# P_10_WIFI_Bluetooth.net
KiCad netlist of a schematic drawn in Altium Designer
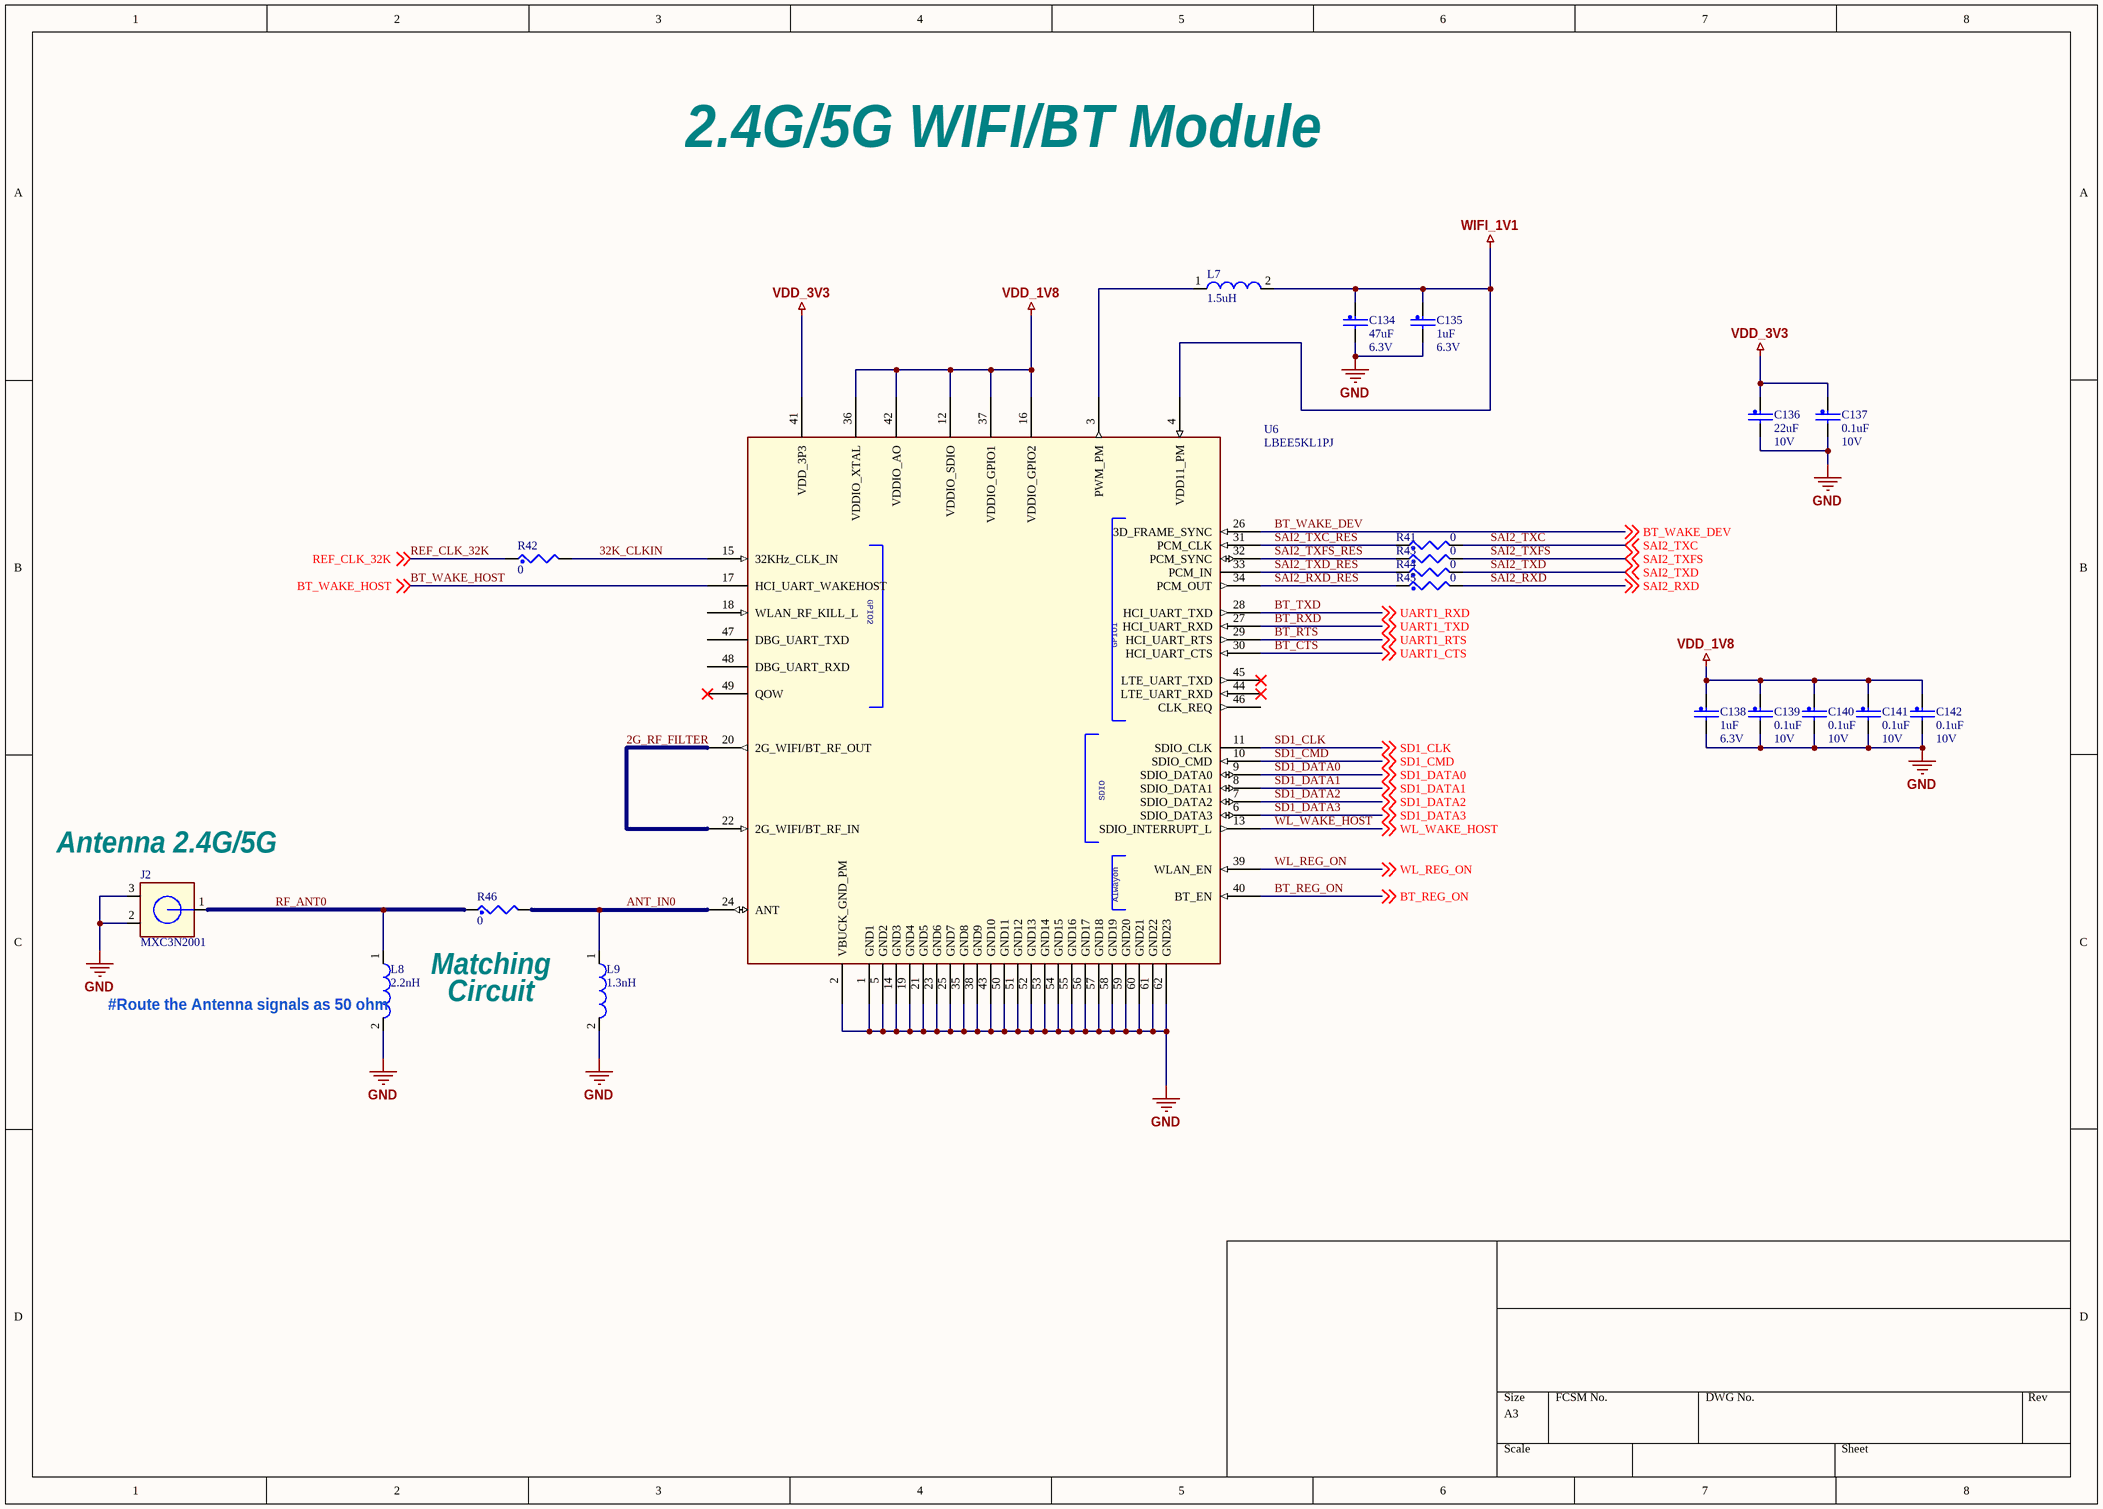
[diagram p0: P[10]WIFI_Bluetooth.SchDoc]

(export (version "E")
  (design (tool "Eeschema 10.0.6"))
  (components
    (comp (ref "C134")
      (value "47uF")
      (footprint "0805_CC")
      (fields (field (name "VOLTAGE") "6.3V"))
      (libsource (lib "AA_iMX8_M_") (part "CAP_NP"))
    )
    (comp (ref "C135")
      (value "1uF")
      (footprint "0201_CC - C")
      (fields (field (name "VOLTAGE") "6.3V"))
      (libsource (lib "AA_iMX8_M_") (part "CAP_NP"))
    )
    (comp (ref "C136")
      (value "22uF")
      (footprint "0603_CC")
      (fields (field (name "VOLTAGE") "10V"))
      (libsource (lib "AA_iMX8_M_") (part "CAP_NP"))
    )
    (comp (ref "C137")
      (value "0.1uF")
      (footprint "0201_CC - C")
      (fields (field (name "VOLTAGE") "10V"))
      (libsource (lib "AA_iMX8_M_") (part "CAP_NP"))
    )
    (comp (ref "C138")
      (value "1uF")
      (footprint "0201_CC - C")
      (fields (field (name "VOLTAGE") "6.3V"))
      (libsource (lib "AA_iMX8_M_") (part "CAP_NP"))
    )
    (comp (ref "C139")
      (value "0.1uF")
      (footprint "0201_CC - C")
      (fields (field (name "VOLTAGE") "10V"))
      (libsource (lib "AA_iMX8_M_") (part "CAP_NP"))
    )
    (comp (ref "C140")
      (value "0.1uF")
      (footprint "0201_CC - C")
      (fields (field (name "VOLTAGE") "10V"))
      (libsource (lib "AA_iMX8_M_") (part "CAP_NP"))
    )
    (comp (ref "C141")
      (value "0.1uF")
      (footprint "0201_CC - C")
      (fields (field (name "VOLTAGE") "10V"))
      (libsource (lib "AA_iMX8_M_") (part "CAP_NP"))
    )
    (comp (ref "C142")
      (value "0.1uF")
      (footprint "0201_CC - C")
      (fields (field (name "VOLTAGE") "10V"))
      (libsource (lib "AA_iMX8_M_") (part "CAP_NP"))
    )
    (comp (ref "J2")
      (value "MXC3N2001")
      (footprint "CON_3_UFL_R_SMT")
      (description "CON 1 COAX SKT SMT 55H AU\\By Arman Arvand")
      (libsource (lib "AA_iMX8_M_") (part "UFL"))
    )
    (comp (ref "L7")
      (value "1.5uH")
      (footprint "INDC2016X100N")
      (libsource (lib "AA_iMX8_M_") (part "INDUCTOR"))
    )
    (comp (ref "L8")
      (value "2.2nH")
      (footprint "0402_CC_IND")
      (libsource (lib "AA_iMX8_M_") (part "INDUCTOR"))
    )
    (comp (ref "L9")
      (value "1.3nH")
      (footprint "0402_CC_IND")
      (libsource (lib "AA_iMX8_M_") (part "INDUCTOR"))
    )
    (comp (ref "R41") (value "0") (footprint "0402_CC") (libsource (lib "AA_iMX8_M_") (part "RES")))
    (comp (ref "R42") (value "0") (footprint "0402_CC") (libsource (lib "AA_iMX8_M_") (part "RES")))
    (comp (ref "R43") (value "0") (footprint "0402_CC") (libsource (lib "AA_iMX8_M_") (part "RES")))
    (comp (ref "R44") (value "0") (footprint "0402_CC") (libsource (lib "AA_iMX8_M_") (part "RES")))
    (comp (ref "R45") (value "0") (footprint "0402_CC") (libsource (lib "AA_iMX8_M_") (part "RES")))
    (comp (ref "R46") (value "0") (footprint "0402_CC") (libsource (lib "AA_iMX8_M_") (part "RES")))
    (comp (ref "U6")
      (value "LBEE5KL1PJ")
      (footprint "LQFN62_0P6_7P6X7P4")
      (description "LBEE5KL1PJ_QFN62\\By Arman Arvand")
      (libsource (lib "AA_iMX8_M_") (part "LBEE5KL1PJ_QFN62"))
    )
  )
  (nets
    (net (code "1") (name "/2G_RF_FILTER") (class "Default")
      (node (ref "U6") (pin "20") (pinfunction "2G_WIFI/BT_RF_OUT_20") (pintype "output"))
      (node (ref "U6") (pin "22") (pinfunction "2G_WIFI/BT_RF_IN_22") (pintype "input"))
    )
    (net (code "2") (name "/32K_CLKIN") (class "Default")
      (node (ref "R42") (pin "2") (pinfunction "2_2") (pintype "passive"))
      (node (ref "U6") (pin "15") (pinfunction "32KHz_CLK_IN_15") (pintype "input"))
    )
    (net (code "3") (name "/ANT_IN0") (class "Default")
      (node (ref "L9") (pin "1") (pinfunction "1_1") (pintype "passive"))
      (node (ref "R46") (pin "2") (pinfunction "2_2") (pintype "passive"))
      (node (ref "U6") (pin "24") (pinfunction "ANT_24") (pintype "bidirectional"))
    )
    (net (code "4") (name "/RF_ANT0") (class "Default")
      (node (ref "J2") (pin "1") (pinfunction "CTR_1") (pintype "passive"))
      (node (ref "L8") (pin "1") (pinfunction "1_1") (pintype "passive"))
      (node (ref "R46") (pin "1") (pinfunction "1_1") (pintype "passive"))
    )
    (net (code "5") (name "/SAI2_RXD_RES") (class "Default")
      (node (ref "R45") (pin "1") (pinfunction "1_1") (pintype "passive"))
      (node (ref "U6") (pin "34") (pinfunction "PCM_OUT_34") (pintype "output"))
    )
    (net (code "6") (name "/SAI2_TXC_RES") (class "Default")
      (node (ref "R41") (pin "1") (pinfunction "1_1") (pintype "passive"))
      (node (ref "U6") (pin "31") (pinfunction "PCM_CLK_31") (pintype "input"))
    )
    (net (code "7") (name "/SAI2_TXD_RES") (class "Default")
      (node (ref "R44") (pin "1") (pinfunction "1_1") (pintype "passive"))
      (node (ref "U6") (pin "33") (pinfunction "PCM_IN_33") (pintype "open_collector"))
    )
    (net (code "8") (name "/SAI2_TXFS_RES") (class "Default")
      (node (ref "R43") (pin "1") (pinfunction "1_1") (pintype "passive"))
      (node (ref "U6") (pin "32") (pinfunction "PCM_SYNC_32") (pintype "bidirectional"))
    )
    (net (code "9") (name "BT_REG_ON") (class "Default")
      (node (ref "U6") (pin "40") (pinfunction "BT_EN_40") (pintype "input"))
    )
    (net (code "10") (name "BT_WAKE_DEV") (class "Default")
      (node (ref "U6") (pin "26") (pinfunction "3D_FRAME_SYNC_26") (pintype "input"))
    )
    (net (code "11") (name "BT_WAKE_HOST") (class "Default")
      (node (ref "U6") (pin "17") (pinfunction "HCI_UART_WAKEHOST_17") (pintype "open_collector"))
    )
    (net (code "12") (name "GND") (class "Default")
      (node (ref "C134") (pin "2") (pinfunction "2_2") (pintype "passive"))
      (node (ref "C135") (pin "2") (pinfunction "2_2") (pintype "passive"))
      (node (ref "C136") (pin "2") (pinfunction "2_2") (pintype "passive"))
      (node (ref "C137") (pin "2") (pinfunction "2_2") (pintype "passive"))
      (node (ref "C138") (pin "2") (pinfunction "2_2") (pintype "passive"))
      (node (ref "C139") (pin "2") (pinfunction "2_2") (pintype "passive"))
      (node (ref "C140") (pin "2") (pinfunction "2_2") (pintype "passive"))
      (node (ref "C141") (pin "2") (pinfunction "2_2") (pintype "passive"))
      (node (ref "C142") (pin "2") (pinfunction "2_2") (pintype "passive"))
      (node (ref "J2") (pin "2") (pinfunction "GND1_2") (pintype "passive"))
      (node (ref "J2") (pin "3") (pinfunction "GND2_3") (pintype "passive"))
      (node (ref "L8") (pin "2") (pinfunction "2_2") (pintype "passive"))
      (node (ref "L9") (pin "2") (pinfunction "2_2") (pintype "passive"))
      (node (ref "U6") (pin "1") (pinfunction "GND1_1") (pintype "power_in"))
      (node (ref "U6") (pin "14") (pinfunction "GND3_14") (pintype "power_in"))
      (node (ref "U6") (pin "19") (pinfunction "GND4_19") (pintype "power_in"))
      (node (ref "U6") (pin "2") (pinfunction "VBUCK_GND_PM_2") (pintype "power_in"))
      (node (ref "U6") (pin "21") (pinfunction "GND5_21") (pintype "power_in"))
      (node (ref "U6") (pin "23") (pinfunction "GND6_23") (pintype "power_in"))
      (node (ref "U6") (pin "25") (pinfunction "GND7_25") (pintype "power_in"))
      (node (ref "U6") (pin "35") (pinfunction "GND8_35") (pintype "power_in"))
      (node (ref "U6") (pin "38") (pinfunction "GND9_38") (pintype "power_in"))
      (node (ref "U6") (pin "43") (pinfunction "GND10_43") (pintype "power_in"))
      (node (ref "U6") (pin "5") (pinfunction "GND2_5") (pintype "power_in"))
      (node (ref "U6") (pin "50") (pinfunction "GND11_50") (pintype "power_in"))
      (node (ref "U6") (pin "51") (pinfunction "GND12_51") (pintype "power_in"))
      (node (ref "U6") (pin "52") (pinfunction "GND13_52") (pintype "power_in"))
      (node (ref "U6") (pin "53") (pinfunction "GND14_53") (pintype "power_in"))
      (node (ref "U6") (pin "54") (pinfunction "GND15_54") (pintype "power_in"))
      (node (ref "U6") (pin "55") (pinfunction "GND16_55") (pintype "power_in"))
      (node (ref "U6") (pin "56") (pinfunction "GND17_56") (pintype "power_in"))
      (node (ref "U6") (pin "57") (pinfunction "GND18_57") (pintype "power_in"))
      (node (ref "U6") (pin "58") (pinfunction "GND19_58") (pintype "power_in"))
      (node (ref "U6") (pin "59") (pinfunction "GND20_59") (pintype "power_in"))
      (node (ref "U6") (pin "60") (pinfunction "GND21_60") (pintype "power_in"))
      (node (ref "U6") (pin "61") (pinfunction "GND22_61") (pintype "power_in"))
      (node (ref "U6") (pin "62") (pinfunction "GND23_62") (pintype "power_in"))
    )
    (net (code "13") (name "Net-(U6-PWM_PM)") (class "Default")
      (node (ref "L7") (pin "1") (pinfunction "1_1") (pintype "passive"))
      (node (ref "U6") (pin "3") (pinfunction "PWM_PM_3") (pintype "output"))
    )
    (net (code "14") (name "REF_CLK_32K") (class "Default")
      (node (ref "R42") (pin "1") (pinfunction "1_1") (pintype "passive"))
    )
    (net (code "15") (name "SAI2_RXD") (class "Default")
      (node (ref "R45") (pin "2") (pinfunction "2_2") (pintype "passive"))
    )
    (net (code "16") (name "SAI2_TXC") (class "Default")
      (node (ref "R41") (pin "2") (pinfunction "2_2") (pintype "passive"))
    )
    (net (code "17") (name "SAI2_TXD") (class "Default")
      (node (ref "R44") (pin "2") (pinfunction "2_2") (pintype "passive"))
    )
    (net (code "18") (name "SAI2_TXFS") (class "Default")
      (node (ref "R43") (pin "2") (pinfunction "2_2") (pintype "passive"))
    )
    (net (code "19") (name "SD1_CLK") (class "Default")
      (node (ref "U6") (pin "11") (pinfunction "SDIO_CLK_11") (pintype "open_collector"))
    )
    (net (code "20") (name "SD1_CMD") (class "Default")
      (node (ref "U6") (pin "10") (pinfunction "SDIO_CMD_10") (pintype "input"))
    )
    (net (code "21") (name "SD1_DATA0") (class "Default")
      (node (ref "U6") (pin "9") (pinfunction "SDIO_DATA0_9") (pintype "bidirectional"))
    )
    (net (code "22") (name "SD1_DATA1") (class "Default")
      (node (ref "U6") (pin "8") (pinfunction "SDIO_DATA1_8") (pintype "bidirectional"))
    )
    (net (code "23") (name "SD1_DATA2") (class "Default")
      (node (ref "U6") (pin "7") (pinfunction "SDIO_DATA2_7") (pintype "bidirectional"))
    )
    (net (code "24") (name "SD1_DATA3") (class "Default")
      (node (ref "U6") (pin "6") (pinfunction "SDIO_DATA3_6") (pintype "bidirectional"))
    )
    (net (code "25") (name "UART1_CTS") (class "Default")
      (node (ref "U6") (pin "30") (pinfunction "HCI_UART_CTS_30") (pintype "input"))
    )
    (net (code "26") (name "UART1_RTS") (class "Default")
      (node (ref "U6") (pin "29") (pinfunction "HCI_UART_RTS_29") (pintype "output"))
    )
    (net (code "27") (name "UART1_RXD") (class "Default")
      (node (ref "U6") (pin "28") (pinfunction "HCI_UART_TXD_28") (pintype "output"))
    )
    (net (code "28") (name "UART1_TXD") (class "Default")
      (node (ref "U6") (pin "27") (pinfunction "HCI_UART_RXD_27") (pintype "input"))
    )
    (net (code "29") (name "VDD_1V8") (class "Default")
      (node (ref "C138") (pin "1") (pinfunction "1_1") (pintype "passive"))
      (node (ref "C139") (pin "1") (pinfunction "1_1") (pintype "passive"))
      (node (ref "C140") (pin "1") (pinfunction "1_1") (pintype "passive"))
      (node (ref "C141") (pin "1") (pinfunction "1_1") (pintype "passive"))
      (node (ref "C142") (pin "1") (pinfunction "1_1") (pintype "passive"))
      (node (ref "U6") (pin "12") (pinfunction "VDDIO_SDIO_12") (pintype "power_in"))
      (node (ref "U6") (pin "16") (pinfunction "VDDIO_GPIO2_16") (pintype "power_in"))
      (node (ref "U6") (pin "36") (pinfunction "VDDIO_XTAL_36") (pintype "power_in"))
      (node (ref "U6") (pin "37") (pinfunction "VDDIO_GPIO1_37") (pintype "power_in"))
      (node (ref "U6") (pin "42") (pinfunction "VDDIO_AO_42") (pintype "power_in"))
    )
    (net (code "30") (name "VDD_3V3") (class "Default")
      (node (ref "C136") (pin "1") (pinfunction "1_1") (pintype "passive"))
      (node (ref "C137") (pin "1") (pinfunction "1_1") (pintype "passive"))
      (node (ref "U6") (pin "41") (pinfunction "VDD_3P3_41") (pintype "power_in"))
    )
    (net (code "31") (name "WIFI_1V1") (class "Default")
      (node (ref "C134") (pin "1") (pinfunction "1_1") (pintype "passive"))
      (node (ref "C135") (pin "1") (pinfunction "1_1") (pintype "passive"))
      (node (ref "L7") (pin "2") (pinfunction "2_2") (pintype "passive"))
      (node (ref "U6") (pin "4") (pinfunction "VDD11_PM_4") (pintype "input"))
    )
    (net (code "32") (name "WL_REG_ON") (class "Default")
      (node (ref "U6") (pin "39") (pinfunction "WLAN_EN_39") (pintype "input"))
    )
    (net (code "33") (name "WL_WAKE_HOST") (class "Default")
      (node (ref "U6") (pin "13") (pinfunction "SDIO_INTERRUPT_L_13") (pintype "output"))
    )
    (net (code "34") (name "unconnected-(U6-CLK_REQ-Pad46)") (class "Default")
      (node (ref "U6") (pin "46") (pinfunction "CLK_REQ_46") (pintype "output"))
    )
    (net (code "35") (name "unconnected-(U6-DBG_UART_RXD-Pad48)") (class "Default")
      (node (ref "U6") (pin "48") (pinfunction "DBG_UART_RXD_48") (pintype "open_collector"))
    )
    (net (code "36") (name "unconnected-(U6-DBG_UART_TXD-Pad47)") (class "Default")
      (node (ref "U6") (pin "47") (pinfunction "DBG_UART_TXD_47") (pintype "open_collector"))
    )
    (net (code "37") (name "unconnected-(U6-LTE_UART_RXD-Pad44)") (class "Default")
      (node (ref "U6") (pin "44") (pinfunction "LTE_UART_RXD_44") (pintype "input+no_connect"))
    )
    (net (code "38") (name "unconnected-(U6-LTE_UART_TXD-Pad45)") (class "Default")
      (node (ref "U6") (pin "45") (pinfunction "LTE_UART_TXD_45") (pintype "output+no_connect"))
    )
    (net (code "39") (name "unconnected-(U6-QOW-Pad49)") (class "Default")
      (node (ref "U6") (pin "49") (pinfunction "QOW_49") (pintype "open_collector+no_connect"))
    )
    (net (code "40") (name "unconnected-(U6-WLAN_RF_KILL_L-Pad18)") (class "Default")
      (node (ref "U6") (pin "18") (pinfunction "WLAN_RF_KILL_L_18") (pintype "input"))
    )
  )
)
